# Sheet1.net
KiCad netlist of a schematic drawn in Altium Designer
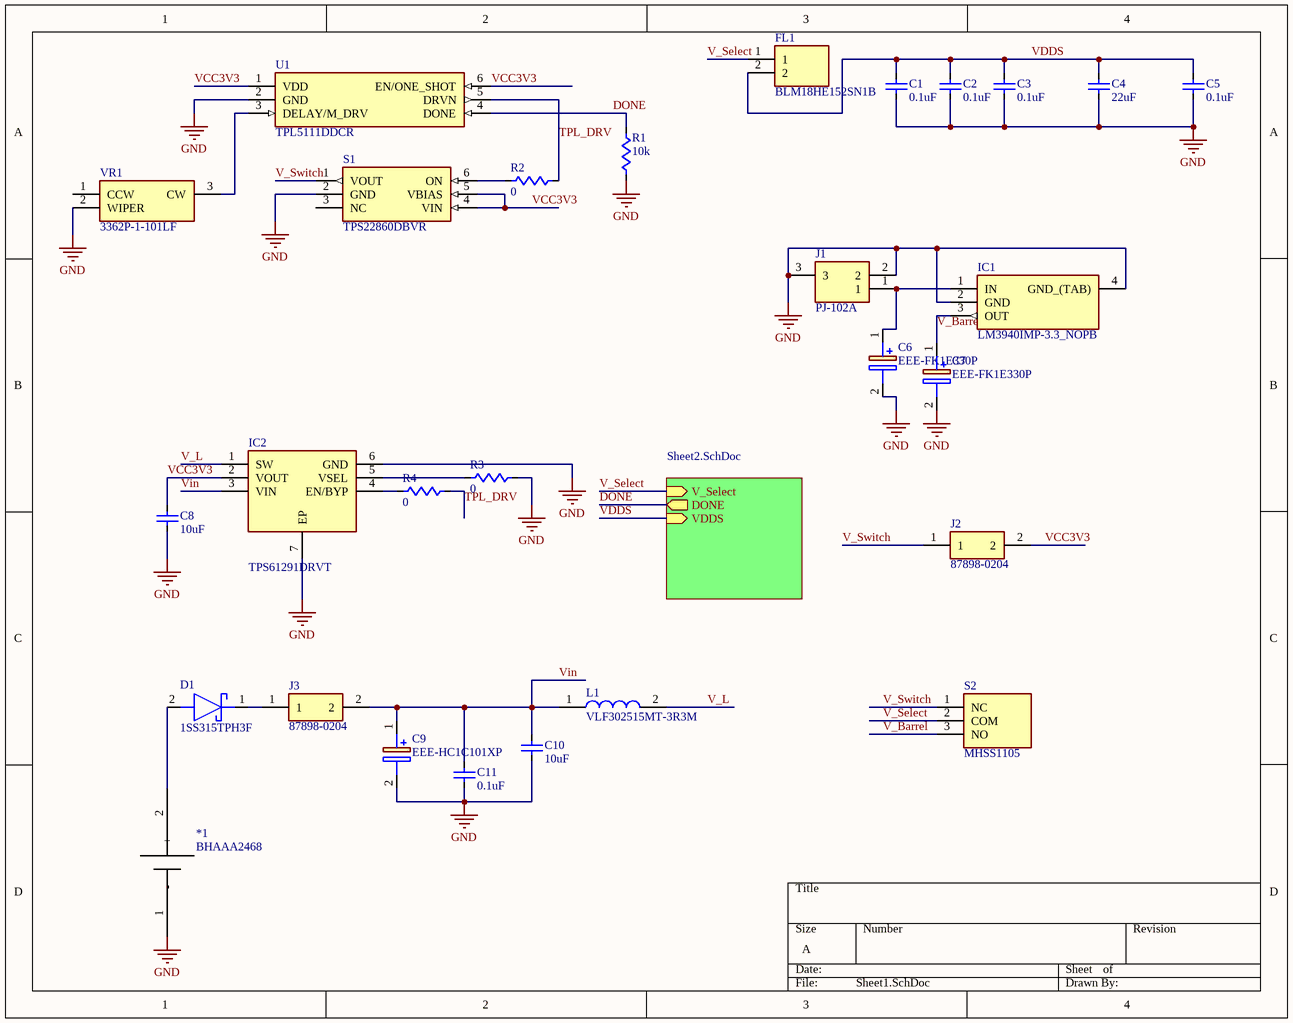
[diagram p0: Sheet1.SchDoc]

(export (version "E")
  (design (tool "Eeschema 10.0.6"))
  (components
    (comp (ref "*1")
      (value "BHAAA2468")
      (footprint "BHAAA2468")
      (libsource (lib "Enviornmental_Sensor") (part "BHAAA2468"))
    )
    (comp (ref "C1")
      (value "0.1uF")
      (footprint "PASSIVE-CAPACITOR-0603")
      (description "Generic Capacitor")
      (fields (field (name "Comment") "Passive-Capacitor (Generic)"))
      (libsource (lib "MasterLib") (part "Passive-Capacitor (Generic)"))
    )
    (comp (ref "C2")
      (value "0.1uF")
      (footprint "PASSIVE-CAPACITOR-0603")
      (description "Generic Capacitor")
      (fields (field (name "Comment") "Passive-Capacitor (Generic)"))
      (libsource (lib "MasterLib") (part "Passive-Capacitor (Generic)"))
    )
    (comp (ref "C3")
      (value "0.1uF")
      (footprint "PASSIVE-CAPACITOR-0603")
      (description "Generic Capacitor")
      (fields (field (name "Comment") "Passive-Capacitor (Generic)"))
      (libsource (lib "MasterLib") (part "Passive-Capacitor (Generic)"))
    )
    (comp (ref "C4")
      (value "22uF")
      (footprint "PASSIVE-CAPACITOR-0603")
      (description "Generic Capacitor")
      (libsource (lib "") (part "Passive-Capacitor (Generic)_1"))
    )
    (comp (ref "C5")
      (value "0.1uF")
      (footprint "PASSIVE-CAPACITOR-0603")
      (description "Generic Capacitor")
      (fields (field (name "Comment") "Passive-Capacitor (Generic)"))
      (libsource (lib "MasterLib") (part "Passive-Capacitor (Generic)"))
    )
    (comp (ref "C6")
      (value "EEE-FK1E330P")
      (footprint "CAPAE660X610N")
      (description "Capacitor Polarised")
      (fields (field (name "MOUSER PART NUMBER") "667-EEE-FK1E330P"))
      (libsource (lib "Enviornmental_Sensor") (part "EEE-FK1E330P"))
    )
    (comp (ref "C7")
      (value "EEE-FK1E330P")
      (footprint "CAPAE660X610N")
      (description "Capacitor Polarised")
      (fields (field (name "MOUSER PART NUMBER") "667-EEE-FK1E330P"))
      (libsource (lib "Enviornmental_Sensor") (part "EEE-FK1E330P"))
    )
    (comp (ref "C8")
      (value "10uF")
      (footprint "PASSIVE-CAPACITOR-0603")
      (description "Generic Capacitor")
      (fields (field (name "Comment") "Passive-Capacitor (Generic)"))
      (libsource (lib "MasterLib") (part "Passive-Capacitor (Generic)"))
    )
    (comp (ref "C9")
      (value "EEE-HC1C101XP")
      (footprint "CAPAE660X800N")
      (description "Capacitor Polarised")
      (fields (field (name "MOUSER PART NUMBER") "667-EEE-HC1C101XP"))
      (libsource (lib "Enviornmental_Sensor") (part "EEE-HC1C101XP"))
    )
    (comp (ref "C10")
      (value "10uF")
      (footprint "PASSIVE-CAPACITOR-0603")
      (description "Generic Capacitor")
      (fields (field (name "Comment") "Passive-Capacitor (Generic)"))
      (libsource (lib "MasterLib") (part "Passive-Capacitor (Generic)"))
    )
    (comp (ref "C11")
      (value "0.1uF")
      (footprint "PASSIVE-CAPACITOR-0603")
      (description "Generic Capacitor")
      (fields (field (name "Comment") "Passive-Capacitor (Generic)"))
      (libsource (lib "MasterLib") (part "Passive-Capacitor (Generic)"))
    )
    (comp (ref "D1")
      (value "1SS315TPH3F")
      (footprint "SOD2513X110N")
      (description "Schottky Diode")
      (fields (field (name "MOUSER PART NUMBER") "757-1SS315TPH3F"))
      (libsource (lib "Enviornmental_Sensor") (part "1SS315TPH3F"))
    )
    (comp (ref "FL1")
      (value "BLM18HE152SN1B")
      (footprint "BEADC1608X95N")
      (description "Filter")
      (libsource (lib "Enviornmental_Sensor") (part "BLM18HE152SN1B"))
    )
    (comp (ref "IC1")
      (value "LM3940IMP-3.3_NOPB")
      (footprint "SOT230P700X180-4N")
      (description "Integrated Circuit")
      (fields
        (field (name "MANUFACTURER_PART_NUMBER") "LM3940IMP-3.3/NOPB")
        (field (name "MOUSER PART NUMBER") "926-LM3940IMP3.3NOPB")
      )
      (libsource (lib "Enviornmental_Sensor") (part "LM3940IMP-3.3_NOPB"))
    )
    (comp (ref "IC2")
      (value "TPS61291DRVT")
      (footprint "SON65P200X200X80-7N")
      (description "Integrated Circuit")
      (fields
        (field (name "MOUSER PART NUMBER") "595-TPS61291DRVT")
        (field (name "RS PART NUMBER") "9143112P")
      )
      (libsource (lib "Enviornmental_Sensor") (part "TPS61291DRVT"))
    )
    (comp (ref "J1")
      (value "PJ-102A")
      (footprint "PJ-102AH")
      (description "Connector")
      (fields (field (name "MOUSER PART NUMBER") "490-PJ-102A"))
      (libsource (lib "Enviornmental_Sensor") (part "PJ-102A"))
    )
    (comp (ref "J2")
      (value "87898-0204")
      (footprint "878980204")
      (description "Connector")
      (fields (field (name "MOUSER PART NUMBER") "538-87898-0204"))
      (libsource (lib "Enviornmental_Sensor") (part "87898-0204"))
    )
    (comp (ref "J3")
      (value "87898-0204")
      (footprint "878980204")
      (description "Connector")
      (fields (field (name "MOUSER PART NUMBER") "538-87898-0204"))
      (libsource (lib "Enviornmental_Sensor") (part "87898-0204"))
    )
    (comp (ref "L1")
      (value "VLF302515MT-3R3M")
      (footprint "VLF302515MT")
      (description "Inductor")
      (fields (field (name "MOUSER PART NUMBER") "810-VLF302515MT-3R3M"))
      (libsource (lib "Enviornmental_Sensor") (part "VLF302515MT-3R3M"))
    )
    (comp (ref "R1")
      (value "10k")
      (footprint "PASSIVE-RESISTOR-0603")
      (description "Generic Resistor")
      (fields (field (name "Comment") "Passive-Resistor (Generic)"))
      (libsource (lib "MasterLib") (part "Passive-Resistor (Generic)"))
    )
    (comp (ref "R2")
      (value "0")
      (footprint "PASSIVE-RESISTOR-0603")
      (description "Generic Resistor")
      (fields (field (name "Comment") "Passive-Resistor (Generic)"))
      (libsource (lib "MasterLib") (part "Passive-Resistor (Generic)"))
    )
    (comp (ref "R3")
      (value "0")
      (footprint "PASSIVE-RESISTOR-0603")
      (description "Generic Resistor")
      (fields (field (name "Comment") "Passive-Resistor (Generic)"))
      (libsource (lib "MasterLib") (part "Passive-Resistor (Generic)"))
    )
    (comp (ref "R4")
      (value "0")
      (footprint "PASSIVE-RESISTOR-0603")
      (description "Generic Resistor")
      (fields (field (name "Comment") "Passive-Resistor (Generic)"))
      (libsource (lib "MasterLib") (part "Passive-Resistor (Generic)"))
    )
    (comp (ref "S1")
      (value "TPS22860DBVR")
      (footprint "SOT95P280X145-6N")
      (description "Switch")
      (fields (field (name "MOUSER PART NUMBER") "595-TPS22860DBVR"))
      (libsource (lib "Enviornmental_Sensor") (part "TPS22860DBVR"))
    )
    (comp (ref "S2")
      (value "MHSS1105")
      (footprint "MHSS1105")
      (description "Switch")
      (fields (field (name "MOUSER PART NUMBER") "642-MHSS1105"))
      (libsource (lib "Enviornmental_Sensor") (part "MHSS1105"))
    )
    (comp (ref "U1")
      (value "TPL5111DDCR")
      (footprint "SOT95P280X110-6N")
      (description "Undefined or Miscellaneous")
      (fields (field (name "MOUSER PART NUMBER") "595-TPL5111DDCR"))
      (libsource (lib "Enviornmental_Sensor") (part "TPL5111DDCR"))
    )
    (comp (ref "VR1")
      (value "3362P-1-101LF")
      (footprint "3362P1101LF")
      (description "Variable Resistor")
      (fields
        (field (name "MOUSER PART NUMBER") "652-3362P-1-101LF")
        (field (name "RS PART NUMBER") "5220877P")
      )
      (libsource (lib "Enviornmental_Sensor") (part "3362P-1-101LF"))
    )
  )
  (nets
    (net (code "1") (name "/DONE") (class "Default")
      (node (ref "R1") (pin "2") (pinfunction "2_2") (pintype "passive"))
      (node (ref "U1") (pin "4") (pinfunction "DONE_4") (pintype "input"))
    )
    (net (code "2") (name "/TPL_DRV") (class "Default")
      (node (ref "R2") (pin "2") (pinfunction "2_2") (pintype "passive"))
      (node (ref "R4") (pin "2") (pinfunction "2_2") (pintype "passive"))
      (node (ref "U1") (pin "5") (pinfunction "DRVN_5") (pintype "output"))
    )
    (net (code "3") (name "/VCC3V3") (class "Default")
      (node (ref "C8") (pin "2") (pinfunction "2_2") (pintype "passive"))
      (node (ref "IC2") (pin "2") (pinfunction "VOUT_2") (pintype "passive"))
      (node (ref "J2") (pin "2") (pinfunction "2_2") (pintype "passive"))
      (node (ref "S1") (pin "4") (pinfunction "VIN_4") (pintype "input"))
      (node (ref "S1") (pin "5") (pinfunction "VBIAS_5") (pintype "input"))
      (node (ref "U1") (pin "1") (pinfunction "VDD_1") (pintype "power_in"))
      (node (ref "U1") (pin "6") (pinfunction "EN/ONE_SHOT_6") (pintype "input"))
    )
    (net (code "4") (name "/VDDS") (class "Default")
      (node (ref "C1") (pin "2") (pinfunction "2_2") (pintype "passive"))
      (node (ref "C2") (pin "2") (pinfunction "2_2") (pintype "passive"))
      (node (ref "C3") (pin "2") (pinfunction "2_2") (pintype "passive"))
      (node (ref "C4") (pin "1") (pinfunction "1_1") (pintype "passive"))
      (node (ref "C5") (pin "2") (pinfunction "2_2") (pintype "passive"))
      (node (ref "FL1") (pin "2") (pinfunction "2_2") (pintype "passive"))
    )
    (net (code "5") (name "/V_Barrel") (class "Default")
      (node (ref "C7") (pin "1") (pinfunction "+_1") (pintype "passive"))
      (node (ref "IC1") (pin "3") (pinfunction "OUT_3") (pintype "output"))
      (node (ref "S2") (pin "3") (pinfunction "NO_3") (pintype "passive"))
    )
    (net (code "6") (name "/V_L") (class "Default")
      (node (ref "IC2") (pin "1") (pinfunction "SW_1") (pintype "passive"))
      (node (ref "L1") (pin "2") (pinfunction "2_2") (pintype "passive"))
    )
    (net (code "7") (name "/V_Select") (class "Default")
      (node (ref "FL1") (pin "1") (pinfunction "1_1") (pintype "passive"))
      (node (ref "S2") (pin "2") (pinfunction "COM_2") (pintype "passive"))
    )
    (net (code "8") (name "/V_Switch") (class "Default")
      (node (ref "J2") (pin "1") (pinfunction "1_1") (pintype "passive"))
      (node (ref "S1") (pin "1") (pinfunction "VOUT_1") (pintype "output"))
      (node (ref "S2") (pin "1") (pinfunction "NC_1") (pintype "passive"))
    )
    (net (code "9") (name "/Vin") (class "Default")
      (node (ref "C10") (pin "2") (pinfunction "2_2") (pintype "passive"))
      (node (ref "C11") (pin "2") (pinfunction "2_2") (pintype "passive"))
      (node (ref "C9") (pin "1") (pinfunction "+_1") (pintype "passive"))
      (node (ref "IC2") (pin "3") (pinfunction "VIN_3") (pintype "passive"))
      (node (ref "J3") (pin "2") (pinfunction "2_2") (pintype "passive"))
      (node (ref "L1") (pin "1") (pinfunction "1_1") (pintype "passive"))
    )
    (net (code "10") (name "GND") (class "Default")
      (node (ref "*1") (pin "1") (pinfunction "-_1") (pintype "passive"))
      (node (ref "C1") (pin "1") (pinfunction "1_1") (pintype "passive"))
      (node (ref "C10") (pin "1") (pinfunction "1_1") (pintype "passive"))
      (node (ref "C11") (pin "1") (pinfunction "1_1") (pintype "passive"))
      (node (ref "C2") (pin "1") (pinfunction "1_1") (pintype "passive"))
      (node (ref "C3") (pin "1") (pinfunction "1_1") (pintype "passive"))
      (node (ref "C4") (pin "2") (pinfunction "2_2") (pintype "passive"))
      (node (ref "C5") (pin "1") (pinfunction "1_1") (pintype "passive"))
      (node (ref "C6") (pin "2") (pinfunction "-_2") (pintype "passive"))
      (node (ref "C7") (pin "2") (pinfunction "-_2") (pintype "passive"))
      (node (ref "C8") (pin "1") (pinfunction "1_1") (pintype "passive"))
      (node (ref "C9") (pin "2") (pinfunction "-_2") (pintype "passive"))
      (node (ref "IC1") (pin "2") (pinfunction "GND_2") (pintype "power_in"))
      (node (ref "IC1") (pin "4") (pinfunction "GND_(TAB)_4") (pintype "power_in"))
      (node (ref "IC2") (pin "6") (pinfunction "GND_6") (pintype "passive"))
      (node (ref "IC2") (pin "7") (pinfunction "EP_7") (pintype "passive"))
      (node (ref "J1") (pin "2") (pinfunction "2_2") (pintype "passive"))
      (node (ref "J1") (pin "3") (pinfunction "3_3") (pintype "passive"))
      (node (ref "R1") (pin "1") (pinfunction "1_1") (pintype "passive"))
      (node (ref "R3") (pin "2") (pinfunction "2_2") (pintype "passive"))
      (node (ref "S1") (pin "2") (pinfunction "GND_2") (pintype "power_in"))
      (node (ref "U1") (pin "2") (pinfunction "GND_2") (pintype "power_in"))
      (node (ref "VR1") (pin "2") (pinfunction "WIPER_2") (pintype "passive"))
    )
    (net (code "11") (name "Net-(*1-+)") (class "Default")
      (node (ref "*1") (pin "2") (pinfunction "+_2") (pintype "passive"))
      (node (ref "D1") (pin "2") (pinfunction "A_2") (pintype "passive"))
    )
    (net (code "12") (name "Net-(C6-+)") (class "Default")
      (node (ref "C6") (pin "1") (pinfunction "+_1") (pintype "passive"))
      (node (ref "IC1") (pin "1") (pinfunction "IN_1") (pintype "power_in"))
      (node (ref "J1") (pin "1") (pinfunction "1_1") (pintype "passive"))
    )
    (net (code "13") (name "Net-(D1-K)") (class "Default")
      (node (ref "D1") (pin "1") (pinfunction "K_1") (pintype "passive"))
      (node (ref "J3") (pin "1") (pinfunction "1_1") (pintype "passive"))
    )
    (net (code "14") (name "Net-(IC2-EN{slash}BYP)") (class "Default")
      (node (ref "IC2") (pin "4") (pinfunction "EN/BYP_4") (pintype "passive"))
      (node (ref "R4") (pin "1") (pinfunction "1_1") (pintype "passive"))
    )
    (net (code "15") (name "Net-(IC2-VSEL)") (class "Default")
      (node (ref "IC2") (pin "5") (pinfunction "VSEL_5") (pintype "passive"))
      (node (ref "R3") (pin "1") (pinfunction "1_1") (pintype "passive"))
    )
    (net (code "16") (name "Net-(S1-ON)") (class "Default")
      (node (ref "R2") (pin "1") (pinfunction "1_1") (pintype "passive"))
      (node (ref "S1") (pin "6") (pinfunction "ON_6") (pintype "input"))
    )
    (net (code "17") (name "Net-(U1-DELAY{slash}M_DRV)") (class "Default")
      (node (ref "U1") (pin "3") (pinfunction "DELAY/M_DRV_3") (pintype "input"))
      (node (ref "VR1") (pin "3") (pinfunction "CW_3") (pintype "passive"))
    )
    (net (code "18") (name "unconnected-(S1-NC-Pad3)") (class "Default")
      (node (ref "S1") (pin "3") (pinfunction "NC_3") (pintype "passive"))
    )
    (net (code "19") (name "unconnected-(VR1-CCW-Pad1)") (class "Default")
      (node (ref "VR1") (pin "1") (pinfunction "CCW_1") (pintype "passive"))
    )
  )
)
